# 02_-_IO.net
KiCad netlist of a schematic drawn in Altium Designer
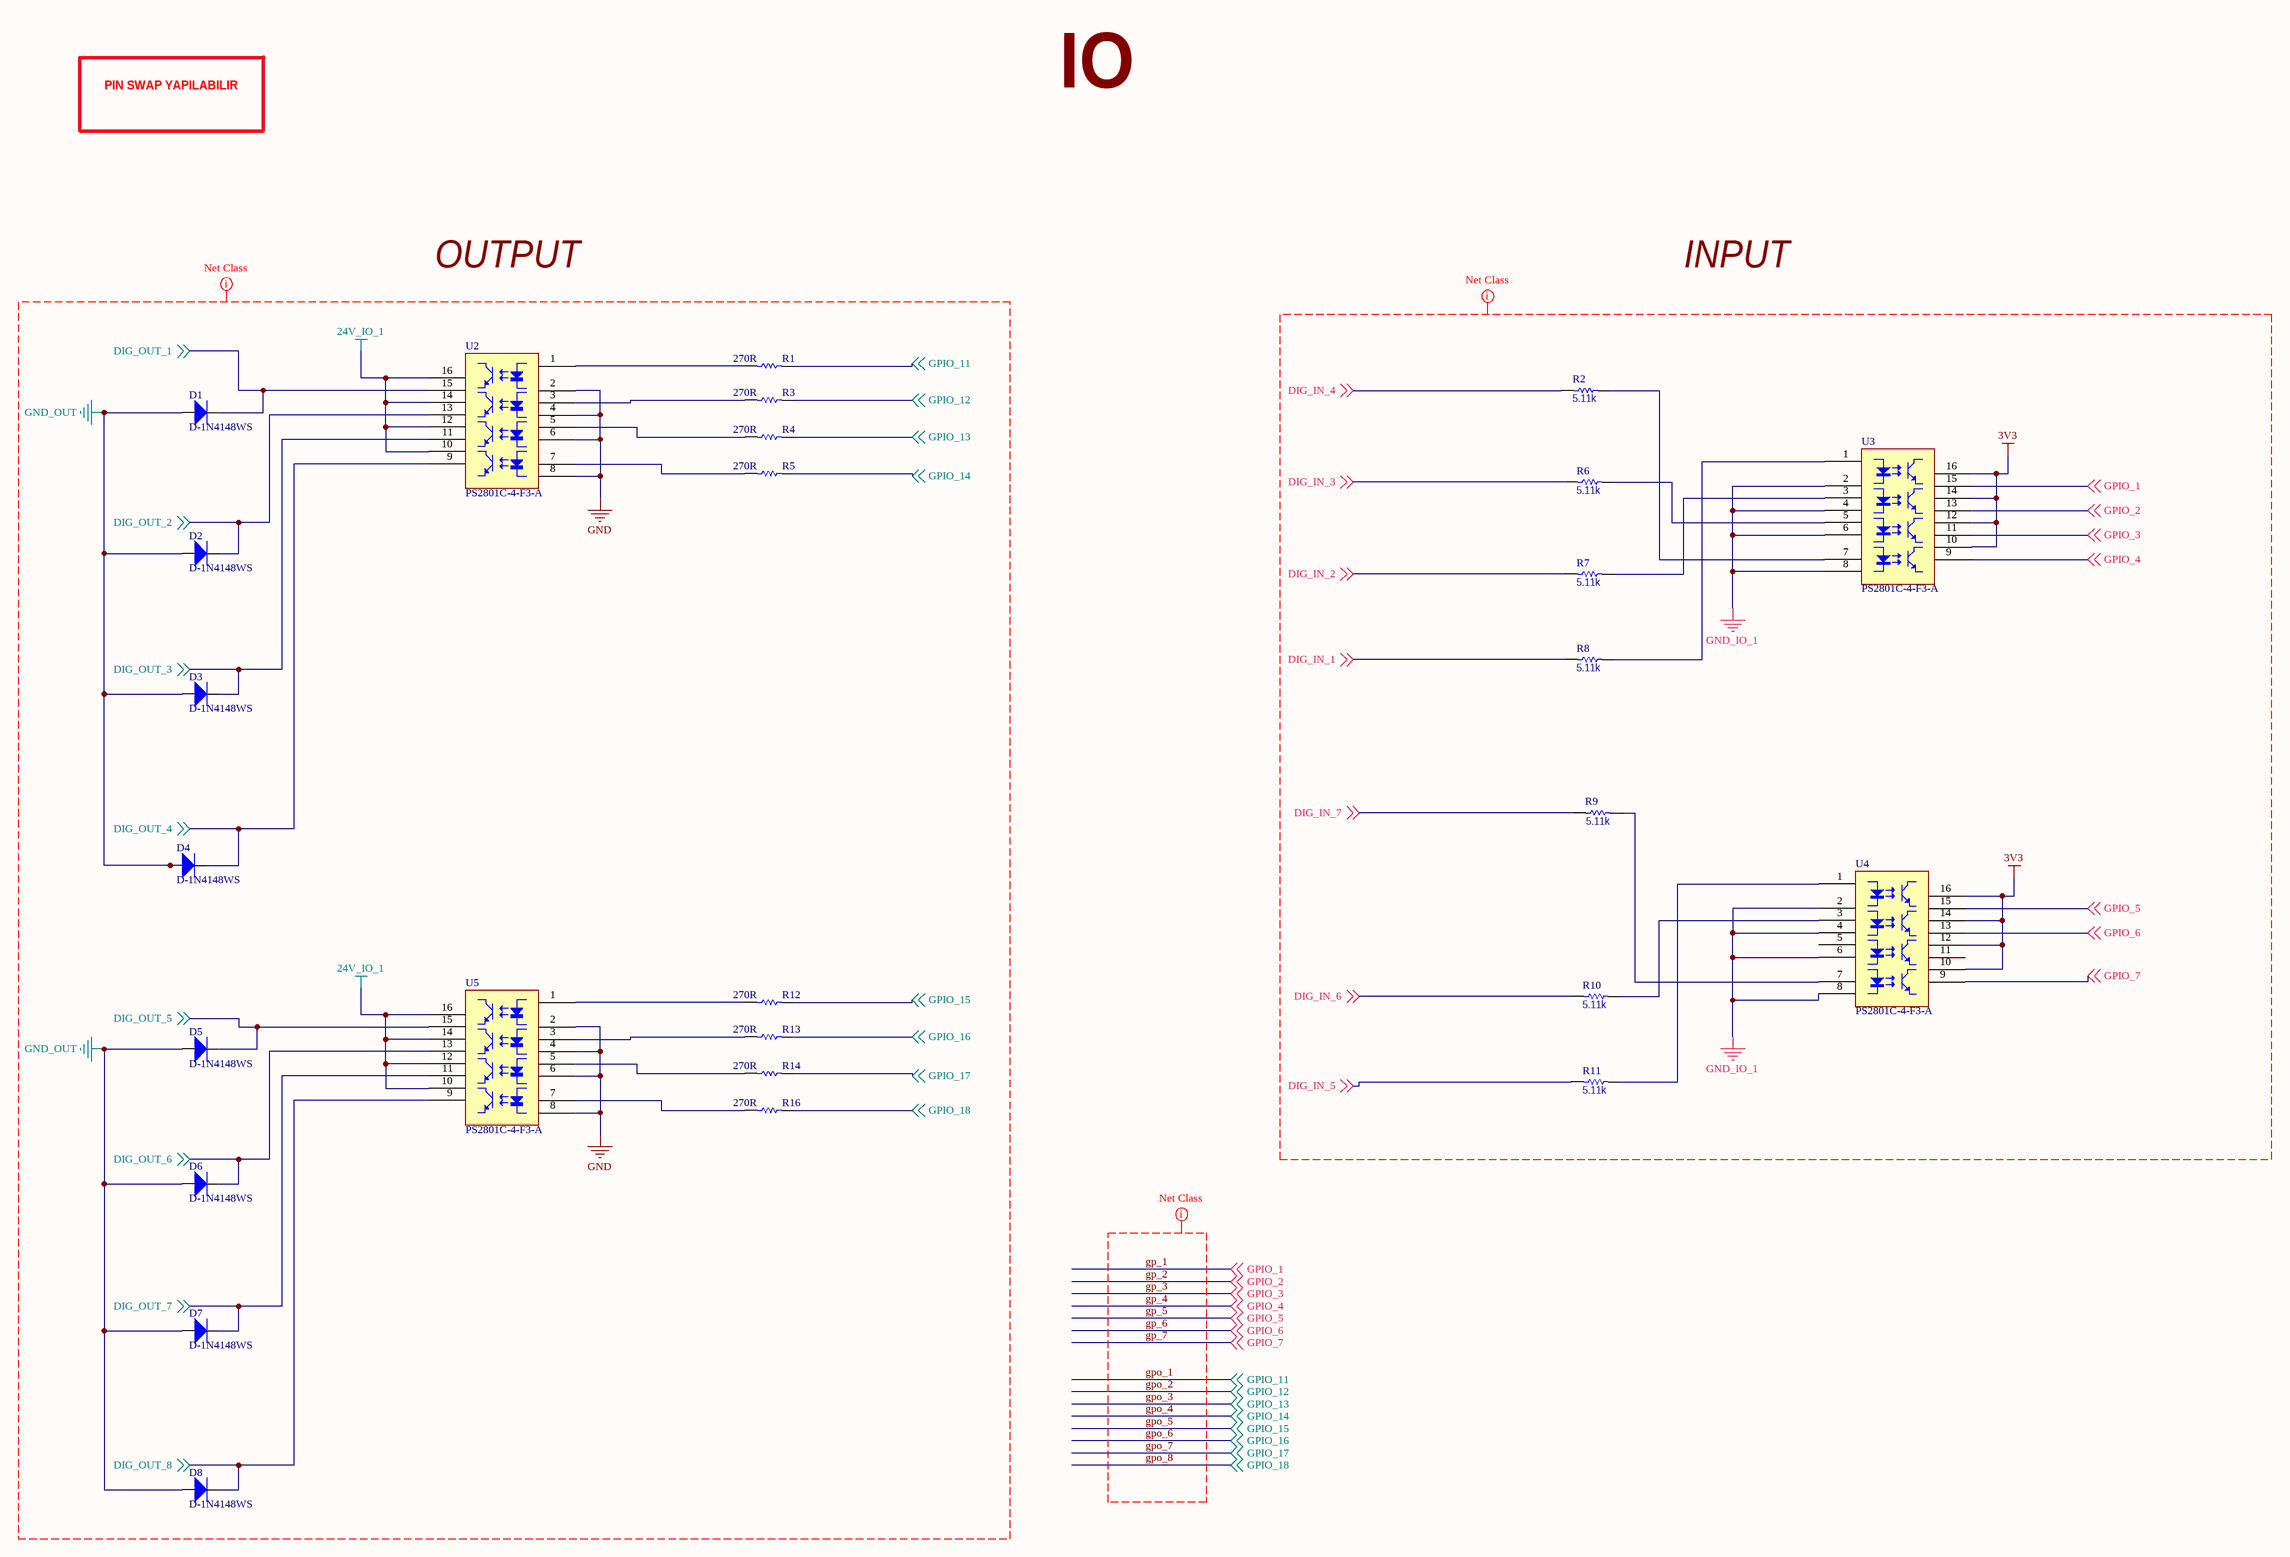
[diagram p0: [02] - IO.SchDoc]

(export (version "E")
  (design (tool "Eeschema 10.0.6"))
  (components
    (comp (ref "D1")
      (value "D-1N4148WS")
      (footprint "SOD-323")
      (description "DIODES INC. - 1N4148WS-7-F - DIODE, SS SWITCH, 75V, 0.2W, SOD323")
      (fields
        (field (name "MANUFACTURER") "DIODES INC.")
        (field (name "MANUFACTURER PART NUMBER") "1N4148WS-7-F")
      )
      (libsource (lib "CPU_STM_080816") (part "D-1N4148WS"))
    )
    (comp (ref "D2")
      (value "D-1N4148WS")
      (footprint "SOD-323")
      (description "DIODES INC. - 1N4148WS-7-F - DIODE, SS SWITCH, 75V, 0.2W, SOD323")
      (fields
        (field (name "MANUFACTURER") "DIODES INC.")
        (field (name "MANUFACTURER PART NUMBER") "1N4148WS-7-F")
      )
      (libsource (lib "CPU_STM_080816") (part "D-1N4148WS"))
    )
    (comp (ref "D3")
      (value "D-1N4148WS")
      (footprint "SOD-323")
      (description "DIODES INC. - 1N4148WS-7-F - DIODE, SS SWITCH, 75V, 0.2W, SOD323")
      (fields
        (field (name "MANUFACTURER") "DIODES INC.")
        (field (name "MANUFACTURER PART NUMBER") "1N4148WS-7-F")
      )
      (libsource (lib "CPU_STM_080816") (part "D-1N4148WS"))
    )
    (comp (ref "D4")
      (value "D-1N4148WS")
      (footprint "SOD-323")
      (description "DIODES INC. - 1N4148WS-7-F - DIODE, SS SWITCH, 75V, 0.2W, SOD323")
      (fields
        (field (name "MANUFACTURER") "DIODES INC.")
        (field (name "MANUFACTURER PART NUMBER") "1N4148WS-7-F")
      )
      (libsource (lib "CPU_STM_080816") (part "D-1N4148WS"))
    )
    (comp (ref "D5")
      (value "D-1N4148WS")
      (footprint "SOD-323")
      (description "DIODES INC. - 1N4148WS-7-F - DIODE, SS SWITCH, 75V, 0.2W, SOD323")
      (fields
        (field (name "MANUFACTURER") "DIODES INC.")
        (field (name "MANUFACTURER PART NUMBER") "1N4148WS-7-F")
      )
      (libsource (lib "CPU_STM_080816") (part "D-1N4148WS"))
    )
    (comp (ref "D6")
      (value "D-1N4148WS")
      (footprint "SOD-323")
      (description "DIODES INC. - 1N4148WS-7-F - DIODE, SS SWITCH, 75V, 0.2W, SOD323")
      (fields
        (field (name "MANUFACTURER") "DIODES INC.")
        (field (name "MANUFACTURER PART NUMBER") "1N4148WS-7-F")
      )
      (libsource (lib "CPU_STM_080816") (part "D-1N4148WS"))
    )
    (comp (ref "D7")
      (value "D-1N4148WS")
      (footprint "SOD-323")
      (description "DIODES INC. - 1N4148WS-7-F - DIODE, SS SWITCH, 75V, 0.2W, SOD323")
      (fields
        (field (name "MANUFACTURER") "DIODES INC.")
        (field (name "MANUFACTURER PART NUMBER") "1N4148WS-7-F")
      )
      (libsource (lib "CPU_STM_080816") (part "D-1N4148WS"))
    )
    (comp (ref "D8")
      (value "D-1N4148WS")
      (footprint "SOD-323")
      (description "DIODES INC. - 1N4148WS-7-F - DIODE, SS SWITCH, 75V, 0.2W, SOD323")
      (fields
        (field (name "MANUFACTURER") "DIODES INC.")
        (field (name "MANUFACTURER PART NUMBER") "1N4148WS-7-F")
      )
      (libsource (lib "CPU_STM_080816") (part "D-1N4148WS"))
    )
    (comp (ref "R1")
      (value "270R")
      (footprint "R0805")
      (description "TE CONNECTIVITY / NEOHM 270R Thin Film")
      (fields
        (field (name "MANUFACTURER") "TE CONNECTIVITY / NEOHM")
        (field (name "MANUFACTURER PART NUMBER") "CPF0805B270RE1")
      )
      (libsource (lib "CPU_STM_080816") (part "R-270R,0805"))
    )
    (comp (ref "R2")
      (value "RES SMD 5.1K")
      (footprint "R1206")
      (description "RES SMD 5.11K OHM 1% 1/2W 1206")
      (fields
        (field (name "MANUFACTURER") "Stackpole Electronics Inc.")
        (field (name "MANUFACTURER PART NUMBER") "RNCP1206FTD5K11")
        (field (name "RESISTANCE (OHMS)") "5.11k")
      )
      (libsource (lib "CPU_STM_080816") (part "R-5.1K,1206"))
    )
    (comp (ref "R3")
      (value "270R")
      (footprint "R0805")
      (description "TE CONNECTIVITY / NEOHM 270R Thin Film")
      (fields
        (field (name "MANUFACTURER") "TE CONNECTIVITY / NEOHM")
        (field (name "MANUFACTURER PART NUMBER") "CPF0805B270RE1")
      )
      (libsource (lib "CPU_STM_080816") (part "R-270R,0805"))
    )
    (comp (ref "R4")
      (value "270R")
      (footprint "R0805")
      (description "TE CONNECTIVITY / NEOHM 270R Thin Film")
      (fields
        (field (name "MANUFACTURER") "TE CONNECTIVITY / NEOHM")
        (field (name "MANUFACTURER PART NUMBER") "CPF0805B270RE1")
      )
      (libsource (lib "CPU_STM_080816") (part "R-270R,0805"))
    )
    (comp (ref "R5")
      (value "270R")
      (footprint "R0805")
      (description "TE CONNECTIVITY / NEOHM 270R Thin Film")
      (fields
        (field (name "MANUFACTURER") "TE CONNECTIVITY / NEOHM")
        (field (name "MANUFACTURER PART NUMBER") "CPF0805B270RE1")
      )
      (libsource (lib "CPU_STM_080816") (part "R-270R,0805"))
    )
    (comp (ref "R6")
      (value "RES SMD 5.1K")
      (footprint "R1206")
      (description "RES SMD 5.11K OHM 1% 1/2W 1206")
      (fields
        (field (name "MANUFACTURER") "Stackpole Electronics Inc.")
        (field (name "MANUFACTURER PART NUMBER") "RNCP1206FTD5K11")
        (field (name "RESISTANCE (OHMS)") "5.11k")
      )
      (libsource (lib "CPU_STM_080816") (part "R-5.1K,1206"))
    )
    (comp (ref "R7")
      (value "RES SMD 5.1K")
      (footprint "R1206")
      (description "RES SMD 5.11K OHM 1% 1/2W 1206")
      (fields
        (field (name "MANUFACTURER") "Stackpole Electronics Inc.")
        (field (name "MANUFACTURER PART NUMBER") "RNCP1206FTD5K11")
        (field (name "RESISTANCE (OHMS)") "5.11k")
      )
      (libsource (lib "CPU_STM_080816") (part "R-5.1K,1206"))
    )
    (comp (ref "R8")
      (value "RES SMD 5.1K")
      (footprint "R1206")
      (description "RES SMD 5.11K OHM 1% 1/2W 1206")
      (fields
        (field (name "MANUFACTURER") "Stackpole Electronics Inc.")
        (field (name "MANUFACTURER PART NUMBER") "RNCP1206FTD5K11")
        (field (name "RESISTANCE (OHMS)") "5.11k")
      )
      (libsource (lib "CPU_STM_080816") (part "R-5.1K,1206"))
    )
    (comp (ref "R9")
      (value "RES SMD 5.1K")
      (footprint "R1206")
      (description "RES SMD 5.11K OHM 1% 1/2W 1206")
      (fields
        (field (name "MANUFACTURER") "Stackpole Electronics Inc.")
        (field (name "MANUFACTURER PART NUMBER") "RNCP1206FTD5K11")
        (field (name "RESISTANCE (OHMS)") "5.11k")
      )
      (libsource (lib "CPU_STM_080816") (part "R-5.1K,1206"))
    )
    (comp (ref "R10")
      (value "RES SMD 5.1K")
      (footprint "R1206")
      (description "RES SMD 5.11K OHM 1% 1/2W 1206")
      (fields
        (field (name "MANUFACTURER") "Stackpole Electronics Inc.")
        (field (name "MANUFACTURER PART NUMBER") "RNCP1206FTD5K11")
        (field (name "RESISTANCE (OHMS)") "5.11k")
      )
      (libsource (lib "CPU_STM_080816") (part "R-5.1K,1206"))
    )
    (comp (ref "R11")
      (value "RES SMD 5.1K")
      (footprint "R1206")
      (description "RES SMD 5.11K OHM 1% 1/2W 1206")
      (fields
        (field (name "MANUFACTURER") "Stackpole Electronics Inc.")
        (field (name "MANUFACTURER PART NUMBER") "RNCP1206FTD5K11")
        (field (name "RESISTANCE (OHMS)") "5.11k")
      )
      (libsource (lib "CPU_STM_080816") (part "R-5.1K,1206"))
    )
    (comp (ref "R12")
      (value "270R")
      (footprint "R0805")
      (description "TE CONNECTIVITY / NEOHM 270R Thin Film")
      (fields
        (field (name "MANUFACTURER") "TE CONNECTIVITY / NEOHM")
        (field (name "MANUFACTURER PART NUMBER") "CPF0805B270RE1")
      )
      (libsource (lib "CPU_STM_080816") (part "R-270R,0805"))
    )
    (comp (ref "R13")
      (value "270R")
      (footprint "R0805")
      (description "TE CONNECTIVITY / NEOHM 270R Thin Film")
      (fields
        (field (name "MANUFACTURER") "TE CONNECTIVITY / NEOHM")
        (field (name "MANUFACTURER PART NUMBER") "CPF0805B270RE1")
      )
      (libsource (lib "CPU_STM_080816") (part "R-270R,0805"))
    )
    (comp (ref "R14")
      (value "270R")
      (footprint "R0805")
      (description "TE CONNECTIVITY / NEOHM 270R Thin Film")
      (fields
        (field (name "MANUFACTURER") "TE CONNECTIVITY / NEOHM")
        (field (name "MANUFACTURER PART NUMBER") "CPF0805B270RE1")
      )
      (libsource (lib "CPU_STM_080816") (part "R-270R,0805"))
    )
    (comp (ref "R16")
      (value "270R")
      (footprint "R0805")
      (description "TE CONNECTIVITY / NEOHM 270R Thin Film")
      (fields
        (field (name "MANUFACTURER") "TE CONNECTIVITY / NEOHM")
        (field (name "MANUFACTURER PART NUMBER") "CPF0805B270RE1")
      )
      (libsource (lib "CPU_STM_080816") (part "R-270R,0805"))
    )
    (comp (ref "U2")
      (value "PS2801C-4-F3-A")
      (footprint "U_16_D LONG")
      (description "NEC - PS2801C-4-F3-A - OPTOCOUPLER, 4X TR O/P, SSOP-16")
      (libsource (lib "CPU_STM_080816") (part "PS2801C-4-F3-A"))
    )
    (comp (ref "U3")
      (value "PS2801C-4-F3-A")
      (footprint "U_16_D LONG")
      (description "NEC - PS2801C-4-F3-A - OPTOCOUPLER, 4X TR O/P, SSOP-16")
      (libsource (lib "CPU_STM_080816") (part "PS2801C-4-F3-A"))
    )
    (comp (ref "U4")
      (value "PS2801C-4-F3-A")
      (footprint "U_16_D LONG")
      (description "NEC - PS2801C-4-F3-A - OPTOCOUPLER, 4X TR O/P, SSOP-16")
      (libsource (lib "CPU_STM_080816") (part "PS2801C-4-F3-A"))
    )
    (comp (ref "U5")
      (value "PS2801C-4-F3-A")
      (footprint "U_16_D LONG")
      (description "NEC - PS2801C-4-F3-A - OPTOCOUPLER, 4X TR O/P, SSOP-16")
      (libsource (lib "CPU_STM_080816") (part "PS2801C-4-F3-A"))
    )
  )
  (nets
    (net (code "1") (name "3V3") (class "Default")
      (node (ref "U3") (pin "10") (pinfunction "10_10") (pintype "passive"))
      (node (ref "U3") (pin "12") (pinfunction "12_12") (pintype "passive"))
      (node (ref "U3") (pin "14") (pinfunction "14_14") (pintype "passive"))
      (node (ref "U3") (pin "16") (pinfunction "16_16") (pintype "passive"))
      (node (ref "U4") (pin "10") (pinfunction "10_10") (pintype "passive"))
      (node (ref "U4") (pin "12") (pinfunction "12_12") (pintype "passive"))
      (node (ref "U4") (pin "14") (pinfunction "14_14") (pintype "passive"))
      (node (ref "U4") (pin "16") (pinfunction "16_16") (pintype "passive"))
    )
    (net (code "2") (name "24V_IO_1") (class "Default")
      (node (ref "U2") (pin "10") (pinfunction "10_10") (pintype "passive"))
      (node (ref "U2") (pin "12") (pinfunction "12_12") (pintype "passive"))
      (node (ref "U2") (pin "14") (pinfunction "14_14") (pintype "passive"))
      (node (ref "U2") (pin "16") (pinfunction "16_16") (pintype "passive"))
      (node (ref "U5") (pin "10") (pinfunction "10_10") (pintype "passive"))
      (node (ref "U5") (pin "12") (pinfunction "12_12") (pintype "passive"))
      (node (ref "U5") (pin "14") (pinfunction "14_14") (pintype "passive"))
      (node (ref "U5") (pin "16") (pinfunction "16_16") (pintype "passive"))
    )
    (net (code "3") (name "DIG_IN_1") (class "Default")
      (node (ref "R8") (pin "1") (pinfunction "1_1") (pintype "passive"))
    )
    (net (code "4") (name "DIG_IN_2") (class "Default")
      (node (ref "R7") (pin "1") (pinfunction "1_1") (pintype "passive"))
    )
    (net (code "5") (name "DIG_IN_3") (class "Default")
      (node (ref "R6") (pin "1") (pinfunction "1_1") (pintype "passive"))
    )
    (net (code "6") (name "DIG_IN_4") (class "Default")
      (node (ref "R2") (pin "1") (pinfunction "1_1") (pintype "passive"))
    )
    (net (code "7") (name "DIG_IN_5") (class "Default")
      (node (ref "R11") (pin "1") (pinfunction "1_1") (pintype "passive"))
    )
    (net (code "8") (name "DIG_IN_6") (class "Default")
      (node (ref "R10") (pin "1") (pinfunction "1_1") (pintype "passive"))
    )
    (net (code "9") (name "DIG_IN_7") (class "Default")
      (node (ref "R9") (pin "1") (pinfunction "1_1") (pintype "passive"))
    )
    (net (code "10") (name "DIG_OUT_1") (class "Default")
      (node (ref "D1") (pin "1") (pinfunction "1_1") (pintype "passive"))
      (node (ref "U2") (pin "15") (pinfunction "15_15") (pintype "passive"))
    )
    (net (code "11") (name "DIG_OUT_2") (class "Default")
      (node (ref "D2") (pin "1") (pinfunction "1_1") (pintype "passive"))
      (node (ref "U2") (pin "13") (pinfunction "13_13") (pintype "passive"))
    )
    (net (code "12") (name "DIG_OUT_3") (class "Default")
      (node (ref "D3") (pin "1") (pinfunction "1_1") (pintype "passive"))
      (node (ref "U2") (pin "11") (pinfunction "11_11") (pintype "passive"))
    )
    (net (code "13") (name "DIG_OUT_4") (class "Default")
      (node (ref "D4") (pin "1") (pinfunction "1_1") (pintype "passive"))
      (node (ref "U2") (pin "9") (pinfunction "9_9") (pintype "passive"))
    )
    (net (code "14") (name "DIG_OUT_5") (class "Default")
      (node (ref "D5") (pin "1") (pinfunction "1_1") (pintype "passive"))
      (node (ref "U5") (pin "15") (pinfunction "15_15") (pintype "passive"))
    )
    (net (code "15") (name "DIG_OUT_6") (class "Default")
      (node (ref "D6") (pin "1") (pinfunction "1_1") (pintype "passive"))
      (node (ref "U5") (pin "13") (pinfunction "13_13") (pintype "passive"))
    )
    (net (code "16") (name "DIG_OUT_7") (class "Default")
      (node (ref "D7") (pin "1") (pinfunction "1_1") (pintype "passive"))
      (node (ref "U5") (pin "11") (pinfunction "11_11") (pintype "passive"))
    )
    (net (code "17") (name "DIG_OUT_8") (class "Default")
      (node (ref "D8") (pin "1") (pinfunction "1_1") (pintype "passive"))
      (node (ref "U5") (pin "9") (pinfunction "9_9") (pintype "passive"))
    )
    (net (code "18") (name "GND") (class "Default")
      (node (ref "U2") (pin "2") (pinfunction "2_2") (pintype "passive"))
      (node (ref "U2") (pin "4") (pinfunction "4_4") (pintype "passive"))
      (node (ref "U2") (pin "6") (pinfunction "6_6") (pintype "passive"))
      (node (ref "U2") (pin "8") (pinfunction "8_8") (pintype "passive"))
      (node (ref "U5") (pin "2") (pinfunction "2_2") (pintype "passive"))
      (node (ref "U5") (pin "4") (pinfunction "4_4") (pintype "passive"))
      (node (ref "U5") (pin "6") (pinfunction "6_6") (pintype "passive"))
      (node (ref "U5") (pin "8") (pinfunction "8_8") (pintype "passive"))
    )
    (net (code "19") (name "GND_IO_1") (class "Default")
      (node (ref "U3") (pin "2") (pinfunction "2_2") (pintype "passive"))
      (node (ref "U3") (pin "4") (pinfunction "4_4") (pintype "passive"))
      (node (ref "U3") (pin "6") (pinfunction "6_6") (pintype "passive"))
      (node (ref "U3") (pin "8") (pinfunction "8_8") (pintype "passive"))
      (node (ref "U4") (pin "2") (pinfunction "2_2") (pintype "passive"))
      (node (ref "U4") (pin "4") (pinfunction "4_4") (pintype "passive"))
      (node (ref "U4") (pin "6") (pinfunction "6_6") (pintype "passive"))
      (node (ref "U4") (pin "8") (pinfunction "8_8") (pintype "passive"))
    )
    (net (code "20") (name "GND_OUT") (class "Default")
      (node (ref "D1") (pin "2") (pinfunction "2_2") (pintype "passive"))
      (node (ref "D2") (pin "2") (pinfunction "2_2") (pintype "passive"))
      (node (ref "D3") (pin "2") (pinfunction "2_2") (pintype "passive"))
      (node (ref "D4") (pin "2") (pinfunction "2_2") (pintype "passive"))
      (node (ref "D5") (pin "2") (pinfunction "2_2") (pintype "passive"))
      (node (ref "D6") (pin "2") (pinfunction "2_2") (pintype "passive"))
      (node (ref "D7") (pin "2") (pinfunction "2_2") (pintype "passive"))
      (node (ref "D8") (pin "2") (pinfunction "2_2") (pintype "passive"))
    )
    (net (code "21") (name "GPIO_1") (class "Default")
      (node (ref "U3") (pin "15") (pinfunction "15_15") (pintype "passive"))
    )
    (net (code "22") (name "GPIO_2") (class "Default")
      (node (ref "U3") (pin "13") (pinfunction "13_13") (pintype "passive"))
    )
    (net (code "23") (name "GPIO_3") (class "Default")
      (node (ref "U3") (pin "11") (pinfunction "11_11") (pintype "passive"))
    )
    (net (code "24") (name "GPIO_4") (class "Default")
      (node (ref "U3") (pin "9") (pinfunction "9_9") (pintype "passive"))
    )
    (net (code "25") (name "GPIO_5") (class "Default")
      (node (ref "U4") (pin "15") (pinfunction "15_15") (pintype "passive"))
    )
    (net (code "26") (name "GPIO_6") (class "Default")
      (node (ref "U4") (pin "13") (pinfunction "13_13") (pintype "passive"))
    )
    (net (code "27") (name "GPIO_7") (class "Default")
      (node (ref "U4") (pin "9") (pinfunction "9_9") (pintype "passive"))
    )
    (net (code "28") (name "GPIO_11") (class "Default")
      (node (ref "R1") (pin "2") (pinfunction "2_2") (pintype "passive"))
    )
    (net (code "29") (name "GPIO_12") (class "Default")
      (node (ref "R3") (pin "2") (pinfunction "2_2") (pintype "passive"))
    )
    (net (code "30") (name "GPIO_13") (class "Default")
      (node (ref "R4") (pin "2") (pinfunction "2_2") (pintype "passive"))
    )
    (net (code "31") (name "GPIO_14") (class "Default")
      (node (ref "R5") (pin "2") (pinfunction "2_2") (pintype "passive"))
    )
    (net (code "32") (name "GPIO_15") (class "Default")
      (node (ref "R12") (pin "2") (pinfunction "2_2") (pintype "passive"))
    )
    (net (code "33") (name "GPIO_16") (class "Default")
      (node (ref "R13") (pin "2") (pinfunction "2_2") (pintype "passive"))
    )
    (net (code "34") (name "GPIO_17") (class "Default")
      (node (ref "R14") (pin "2") (pinfunction "2_2") (pintype "passive"))
    )
    (net (code "35") (name "GPIO_18") (class "Default")
      (node (ref "R16") (pin "2") (pinfunction "2_2") (pintype "passive"))
    )
    (net (code "36") (name "Net-(R1-Pad1)") (class "Default")
      (node (ref "R1") (pin "1") (pinfunction "1_1") (pintype "passive"))
      (node (ref "U2") (pin "1") (pinfunction "1_1") (pintype "passive"))
    )
    (net (code "37") (name "Net-(R2-Pad2)") (class "Default")
      (node (ref "R2") (pin "2") (pinfunction "2_2") (pintype "passive"))
      (node (ref "U3") (pin "7") (pinfunction "7_7") (pintype "passive"))
    )
    (net (code "38") (name "Net-(R3-Pad1)") (class "Default")
      (node (ref "R3") (pin "1") (pinfunction "1_1") (pintype "passive"))
      (node (ref "U2") (pin "3") (pinfunction "3_3") (pintype "passive"))
    )
    (net (code "39") (name "Net-(R4-Pad1)") (class "Default")
      (node (ref "R4") (pin "1") (pinfunction "1_1") (pintype "passive"))
      (node (ref "U2") (pin "5") (pinfunction "5_5") (pintype "passive"))
    )
    (net (code "40") (name "Net-(R5-Pad1)") (class "Default")
      (node (ref "R5") (pin "1") (pinfunction "1_1") (pintype "passive"))
      (node (ref "U2") (pin "7") (pinfunction "7_7") (pintype "passive"))
    )
    (net (code "41") (name "Net-(R6-Pad2)") (class "Default")
      (node (ref "R6") (pin "2") (pinfunction "2_2") (pintype "passive"))
      (node (ref "U3") (pin "5") (pinfunction "5_5") (pintype "passive"))
    )
    (net (code "42") (name "Net-(R7-Pad2)") (class "Default")
      (node (ref "R7") (pin "2") (pinfunction "2_2") (pintype "passive"))
      (node (ref "U3") (pin "3") (pinfunction "3_3") (pintype "passive"))
    )
    (net (code "43") (name "Net-(R8-Pad2)") (class "Default")
      (node (ref "R8") (pin "2") (pinfunction "2_2") (pintype "passive"))
      (node (ref "U3") (pin "1") (pinfunction "1_1") (pintype "passive"))
    )
    (net (code "44") (name "Net-(R9-Pad2)") (class "Default")
      (node (ref "R9") (pin "2") (pinfunction "2_2") (pintype "passive"))
      (node (ref "U4") (pin "7") (pinfunction "7_7") (pintype "passive"))
    )
    (net (code "45") (name "Net-(R10-Pad2)") (class "Default")
      (node (ref "R10") (pin "2") (pinfunction "2_2") (pintype "passive"))
      (node (ref "U4") (pin "3") (pinfunction "3_3") (pintype "passive"))
    )
    (net (code "46") (name "Net-(R11-Pad2)") (class "Default")
      (node (ref "R11") (pin "2") (pinfunction "2_2") (pintype "passive"))
      (node (ref "U4") (pin "1") (pinfunction "1_1") (pintype "passive"))
    )
    (net (code "47") (name "Net-(R12-Pad1)") (class "Default")
      (node (ref "R12") (pin "1") (pinfunction "1_1") (pintype "passive"))
      (node (ref "U5") (pin "1") (pinfunction "1_1") (pintype "passive"))
    )
    (net (code "48") (name "Net-(R13-Pad1)") (class "Default")
      (node (ref "R13") (pin "1") (pinfunction "1_1") (pintype "passive"))
      (node (ref "U5") (pin "3") (pinfunction "3_3") (pintype "passive"))
    )
    (net (code "49") (name "Net-(R14-Pad1)") (class "Default")
      (node (ref "R14") (pin "1") (pinfunction "1_1") (pintype "passive"))
      (node (ref "U5") (pin "5") (pinfunction "5_5") (pintype "passive"))
    )
    (net (code "50") (name "Net-(R16-Pad1)") (class "Default")
      (node (ref "R16") (pin "1") (pinfunction "1_1") (pintype "passive"))
      (node (ref "U5") (pin "7") (pinfunction "7_7") (pintype "passive"))
    )
    (net (code "51") (name "unconnected-(U4-Pad5)") (class "Default")
      (node (ref "U4") (pin "5") (pinfunction "5_5") (pintype "passive"))
    )
    (net (code "52") (name "unconnected-(U4-Pad11)") (class "Default")
      (node (ref "U4") (pin "11") (pinfunction "11_11") (pintype "passive"))
    )
  )
)
